# Microcontroller_8051_2.net
KiCad netlist of a schematic drawn in Altium Designer
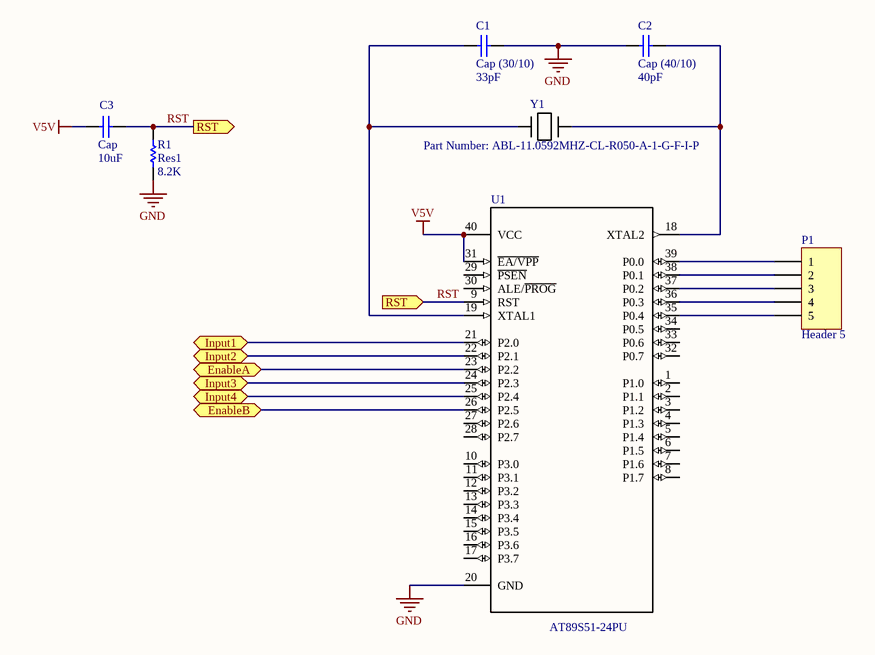
[diagram p0: Microcontroller_8051_2.SchDoc]

(export (version "E")
  (design (tool "Eeschema 10.0.6"))
  (components
    (comp (ref "C1")
      (value "Cap (30/10)")
      (footprint "RAD-0.3")
      (description "Capacitor")
      (fields (field (name "ALTIUM_VALUE") "33pF") (field (name "PUBLISHER") "Altium Limited"))
      (libsource (lib "Miscellaneous Devices") (part "Cap"))
    )
    (comp (ref "C2")
      (value "Cap (40/10)")
      (footprint "RAD-0.3")
      (description "Capacitor")
      (fields (field (name "ALTIUM_VALUE") "40pF") (field (name "PUBLISHER") "Altium Limited"))
      (libsource (lib "Miscellaneous Devices") (part "Cap"))
    )
    (comp (ref "C3")
      (value "Cap")
      (footprint "RAD-0.3")
      (description "Capacitor")
      (fields (field (name "ALTIUM_VALUE") "10uF") (field (name "PUBLISHER") "Altium Limited"))
      (libsource (lib "Miscellaneous Devices") (part "Cap"))
    )
    (comp (ref "P1")
      (value "Header 5")
      (footprint "HDR1X5")
      (description "Header, 5-Pin")
      (fields (field (name "PUBLISHER") "Altium Limited"))
      (libsource (lib "Miscellaneous Connectors") (part "Header 5"))
    )
    (comp (ref "R1")
      (value "Res1")
      (footprint "AXIAL-0.3")
      (description "Resistor")
      (fields (field (name "ALTIUM_VALUE") "8.2K") (field (name "PUBLISHER") "Altium Limited"))
      (libsource (lib "Miscellaneous Devices") (part "Res1"))
    )
    (comp (ref "U1")
      (value "AT89S51-24PU")
      (footprint "DIP254P1524X482-40")
      (description "AT89S Series 24 MHz 4 KB Flash 128 B SRAM 8-Bit Microcontroller - DIP-40")
      (fields (field (name "MF") "Microchip") (field (name "DIGI-KEY_PART_NUMBER") "AT89S51-24PU-ND"))
      (libsource (lib "AT89S51-24PU") (part "AT89S51-24PU"))
    )
    (comp (ref "Y1")
      (value "Part Number: ABL-11.0592MHZ-CL-R050-A-1-G-F-I-P")
      (footprint "ABL_Series")
      (description "No Description Available")
      (fields
        (field (name "MANUFACTURER_PART_NUMBER") "ABL-11.0592MHZ-CL-R050-A-1-G-F-I-P")
        (field (name "COPYRIGHT") "Copyright (C) 2018 Accelerated Designs. All rights reserved")
      )
      (libsource (lib "2019-03-01_21-49-29") (part "ABL-11.0592MHZ-C"))
    )
  )
  (nets
    (net (code "1") (name "/EnableA") (class "Default")
      (node (ref "U1") (pin "23") (pinfunction "P2.2_23") (pintype "bidirectional"))
    )
    (net (code "2") (name "/EnableB") (class "Default")
      (node (ref "U1") (pin "26") (pinfunction "P2.5_26") (pintype "bidirectional"))
    )
    (net (code "3") (name "/Input1") (class "Default")
      (node (ref "U1") (pin "21") (pinfunction "P2.0_21") (pintype "bidirectional"))
    )
    (net (code "4") (name "/Input2") (class "Default")
      (node (ref "U1") (pin "22") (pinfunction "P2.1_22") (pintype "bidirectional"))
    )
    (net (code "5") (name "/Input3") (class "Default")
      (node (ref "U1") (pin "24") (pinfunction "P2.3_24") (pintype "bidirectional"))
    )
    (net (code "6") (name "/Input4") (class "Default")
      (node (ref "U1") (pin "25") (pinfunction "P2.4_25") (pintype "bidirectional"))
    )
    (net (code "7") (name "/RST") (class "Default")
      (node (ref "C3") (pin "1") (pinfunction "1_1") (pintype "passive"))
      (node (ref "R1") (pin "1") (pinfunction "1_1") (pintype "passive"))
      (node (ref "U1") (pin "9") (pinfunction "RST_9") (pintype "input"))
    )
    (net (code "8") (name "GND") (class "Default")
      (node (ref "C1") (pin "2") (pinfunction "2_2") (pintype "passive"))
      (node (ref "C2") (pin "1") (pinfunction "1_1") (pintype "passive"))
      (node (ref "R1") (pin "2") (pinfunction "2_2") (pintype "passive"))
      (node (ref "U1") (pin "20") (pinfunction "GND_20") (pintype "passive"))
    )
    (net (code "9") (name "Net-(U1-P0.0)") (class "Default")
      (node (ref "P1") (pin "1") (pinfunction "1_1") (pintype "passive"))
      (node (ref "U1") (pin "39") (pinfunction "P0.0_39") (pintype "bidirectional"))
    )
    (net (code "10") (name "Net-(U1-P0.1)") (class "Default")
      (node (ref "P1") (pin "2") (pinfunction "2_2") (pintype "passive"))
      (node (ref "U1") (pin "38") (pinfunction "P0.1_38") (pintype "bidirectional"))
    )
    (net (code "11") (name "Net-(U1-P0.2)") (class "Default")
      (node (ref "P1") (pin "3") (pinfunction "3_3") (pintype "passive"))
      (node (ref "U1") (pin "37") (pinfunction "P0.2_37") (pintype "bidirectional"))
    )
    (net (code "12") (name "Net-(U1-P0.3)") (class "Default")
      (node (ref "P1") (pin "4") (pinfunction "4_4") (pintype "passive"))
      (node (ref "U1") (pin "36") (pinfunction "P0.3_36") (pintype "bidirectional"))
    )
    (net (code "13") (name "Net-(U1-P0.4)") (class "Default")
      (node (ref "P1") (pin "5") (pinfunction "5_5") (pintype "passive"))
      (node (ref "U1") (pin "35") (pinfunction "P0.4_35") (pintype "bidirectional"))
    )
    (net (code "14") (name "Net-(U1-XTAL1)") (class "Default")
      (node (ref "C1") (pin "1") (pinfunction "1_1") (pintype "passive"))
      (node (ref "U1") (pin "19") (pinfunction "XTAL1_19") (pintype "input"))
      (node (ref "Y1") (pin "1") (pinfunction "1_1") (pintype "passive"))
    )
    (net (code "15") (name "Net-(U1-XTAL2)") (class "Default")
      (node (ref "C2") (pin "2") (pinfunction "2_2") (pintype "passive"))
      (node (ref "U1") (pin "18") (pinfunction "XTAL2_18") (pintype "output"))
      (node (ref "Y1") (pin "2") (pinfunction "2_2") (pintype "passive"))
    )
    (net (code "16") (name "V5V") (class "Default")
      (node (ref "C3") (pin "2") (pinfunction "2_2") (pintype "passive"))
      (node (ref "U1") (pin "31") (pinfunction "~{EA/VPP}_31") (pintype "input"))
      (node (ref "U1") (pin "40") (pinfunction "VCC_40") (pintype "power_in"))
    )
    (net (code "17") (name "unconnected-(U1-ALE{slash}~{PROG}-Pad30)") (class "Default")
      (node (ref "U1") (pin "30") (pinfunction "ALE/~{PROG}_30") (pintype "input"))
    )
    (net (code "18") (name "unconnected-(U1-P0.5-Pad34)") (class "Default")
      (node (ref "U1") (pin "34") (pinfunction "P0.5_34") (pintype "bidirectional"))
    )
    (net (code "19") (name "unconnected-(U1-P0.6-Pad33)") (class "Default")
      (node (ref "U1") (pin "33") (pinfunction "P0.6_33") (pintype "bidirectional"))
    )
    (net (code "20") (name "unconnected-(U1-P0.7-Pad32)") (class "Default")
      (node (ref "U1") (pin "32") (pinfunction "P0.7_32") (pintype "bidirectional"))
    )
    (net (code "21") (name "unconnected-(U1-P1.0-Pad1)") (class "Default")
      (node (ref "U1") (pin "1") (pinfunction "P1.0_1") (pintype "bidirectional"))
    )
    (net (code "22") (name "unconnected-(U1-P1.1-Pad2)") (class "Default")
      (node (ref "U1") (pin "2") (pinfunction "P1.1_2") (pintype "bidirectional"))
    )
    (net (code "23") (name "unconnected-(U1-P1.2-Pad3)") (class "Default")
      (node (ref "U1") (pin "3") (pinfunction "P1.2_3") (pintype "bidirectional"))
    )
    (net (code "24") (name "unconnected-(U1-P1.3-Pad4)") (class "Default")
      (node (ref "U1") (pin "4") (pinfunction "P1.3_4") (pintype "bidirectional"))
    )
    (net (code "25") (name "unconnected-(U1-P1.4-Pad5)") (class "Default")
      (node (ref "U1") (pin "5") (pinfunction "P1.4_5") (pintype "bidirectional"))
    )
    (net (code "26") (name "unconnected-(U1-P1.5-Pad6)") (class "Default")
      (node (ref "U1") (pin "6") (pinfunction "P1.5_6") (pintype "bidirectional"))
    )
    (net (code "27") (name "unconnected-(U1-P1.6-Pad7)") (class "Default")
      (node (ref "U1") (pin "7") (pinfunction "P1.6_7") (pintype "bidirectional"))
    )
    (net (code "28") (name "unconnected-(U1-P1.7-Pad8)") (class "Default")
      (node (ref "U1") (pin "8") (pinfunction "P1.7_8") (pintype "bidirectional"))
    )
    (net (code "29") (name "unconnected-(U1-P2.6-Pad27)") (class "Default")
      (node (ref "U1") (pin "27") (pinfunction "P2.6_27") (pintype "bidirectional"))
    )
    (net (code "30") (name "unconnected-(U1-P2.7-Pad28)") (class "Default")
      (node (ref "U1") (pin "28") (pinfunction "P2.7_28") (pintype "bidirectional"))
    )
    (net (code "31") (name "unconnected-(U1-P3.0-Pad10)") (class "Default")
      (node (ref "U1") (pin "10") (pinfunction "P3.0_10") (pintype "bidirectional"))
    )
    (net (code "32") (name "unconnected-(U1-P3.1-Pad11)") (class "Default")
      (node (ref "U1") (pin "11") (pinfunction "P3.1_11") (pintype "bidirectional"))
    )
    (net (code "33") (name "unconnected-(U1-P3.2-Pad12)") (class "Default")
      (node (ref "U1") (pin "12") (pinfunction "P3.2_12") (pintype "bidirectional"))
    )
    (net (code "34") (name "unconnected-(U1-P3.3-Pad13)") (class "Default")
      (node (ref "U1") (pin "13") (pinfunction "P3.3_13") (pintype "bidirectional"))
    )
    (net (code "35") (name "unconnected-(U1-P3.4-Pad14)") (class "Default")
      (node (ref "U1") (pin "14") (pinfunction "P3.4_14") (pintype "bidirectional"))
    )
    (net (code "36") (name "unconnected-(U1-P3.5-Pad15)") (class "Default")
      (node (ref "U1") (pin "15") (pinfunction "P3.5_15") (pintype "bidirectional"))
    )
    (net (code "37") (name "unconnected-(U1-P3.6-Pad16)") (class "Default")
      (node (ref "U1") (pin "16") (pinfunction "P3.6_16") (pintype "bidirectional"))
    )
    (net (code "38") (name "unconnected-(U1-P3.7-Pad17)") (class "Default")
      (node (ref "U1") (pin "17") (pinfunction "P3.7_17") (pintype "bidirectional"))
    )
    (net (code "39") (name "unconnected-(U1-~{PSEN}-Pad29)") (class "Default")
      (node (ref "U1") (pin "29") (pinfunction "~{PSEN}_29") (pintype "input"))
    )
  )
)
